# ASCII_13_USB3_0_power.net
KiCad netlist of a schematic drawn in Altium Designer
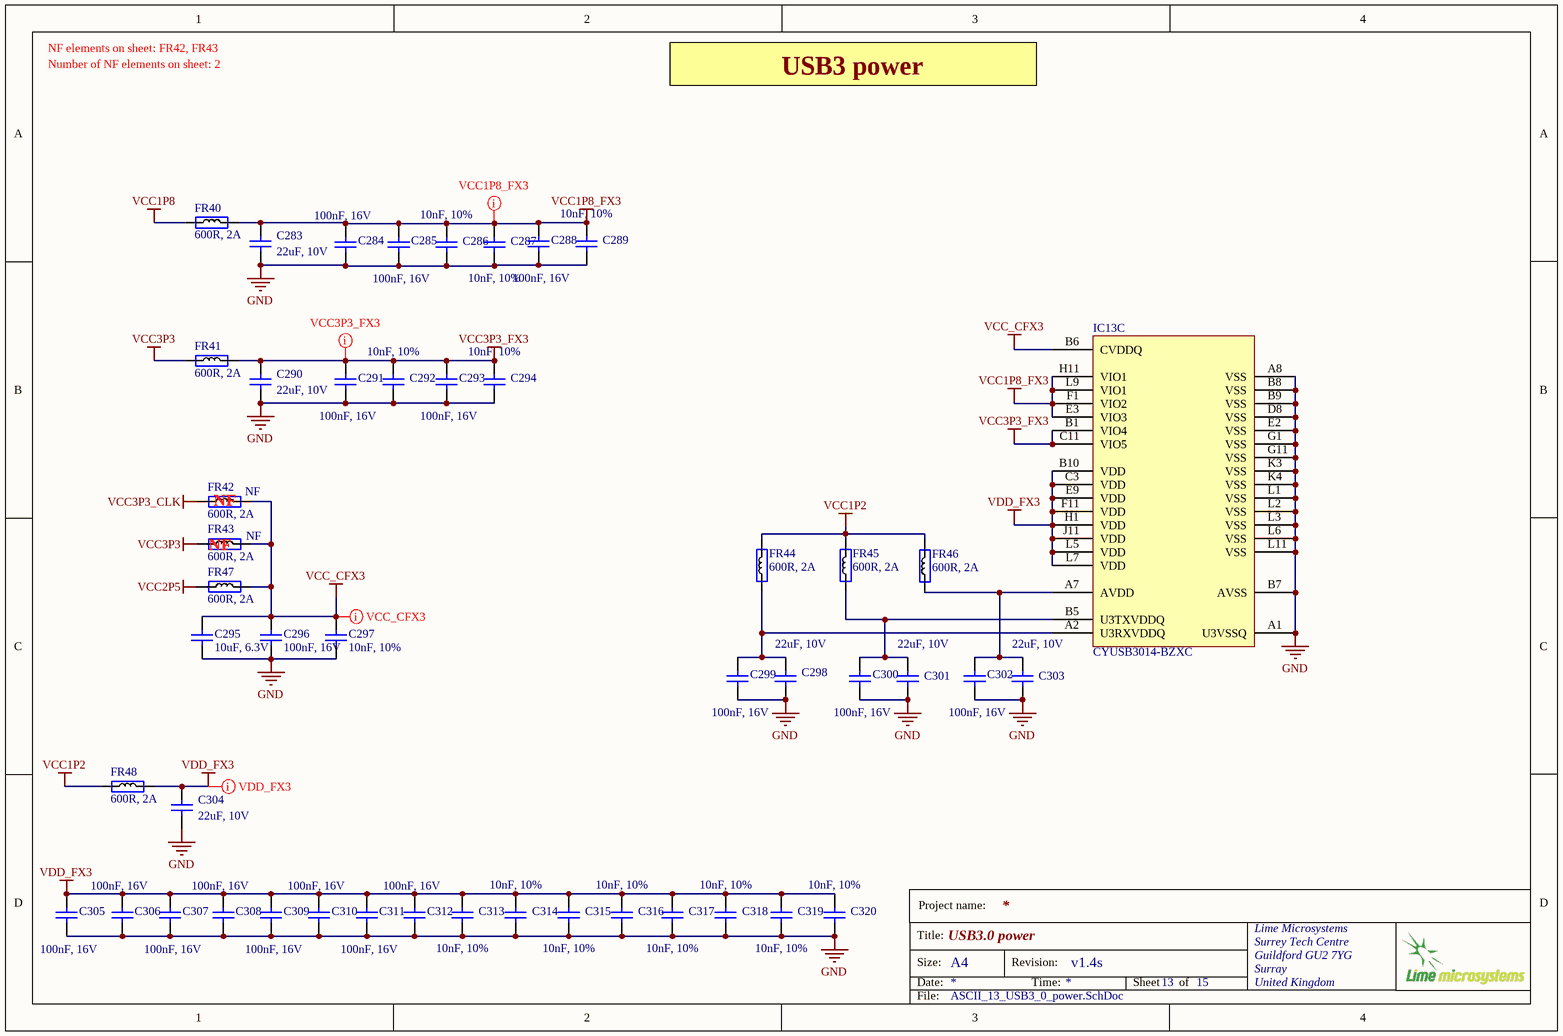
[diagram p0: ASCII_13_USB3_0_power.SchDoc]

(export (version "E")
  (design (tool "Eeschema 10.0.6"))
  (components
    (comp (ref "C283")
      (value "22uF, 10V")
      (footprint "CAP0603")
      (fields (field (name "TOLERANCE") "20 %") (field (name "MANUFACTURER") "TDK"))
      (libsource (lib "LimeFPGAboard_schLib") (part "Cap_0603"))
    )
    (comp (ref "C284")
      (value "100nF, 16V")
      (footprint "CAP0402")
      (fields
        (field (name "TOLERANCE") "10 %")
        (field (name "MANUFACTURER") "Murata Electronics")
        (field (name "MANUFACTURER PART NUMBER") "GRM155R71C104KA88D")
      )
      (libsource (lib "LimeFPGAboard_schLib") (part "Cap_0603"))
    )
    (comp (ref "C285")
      (value "100nF, 16V")
      (footprint "CAP0402")
      (fields
        (field (name "TOLERANCE") "10 %")
        (field (name "MANUFACTURER") "Murata Electronics")
        (field (name "MANUFACTURER PART NUMBER") "GRM155R71C104KA88D")
      )
      (libsource (lib "LimeFPGAboard_schLib") (part "Cap_0603"))
    )
    (comp (ref "C286")
      (value "10nF, 10%")
      (footprint "CAP0402")
      (fields (field (name "TOLERANCE") "±10%") (field (name "MANUFACTURER") "Yageo"))
      (libsource (lib "LimeFPGAboard_schLib") (part "Cap_0603"))
    )
    (comp (ref "C287")
      (value "10nF, 10%")
      (footprint "CAP0402")
      (fields (field (name "TOLERANCE") "±10%") (field (name "MANUFACTURER") "Yageo"))
      (libsource (lib "LimeFPGAboard_schLib") (part "Cap_0603"))
    )
    (comp (ref "C288")
      (value "100nF, 16V")
      (footprint "CAP0402")
      (fields
        (field (name "TOLERANCE") "10 %")
        (field (name "MANUFACTURER") "Murata Electronics")
        (field (name "MANUFACTURER PART NUMBER") "GRM155R71C104KA88D")
      )
      (libsource (lib "LimeFPGAboard_schLib") (part "Cap_0603"))
    )
    (comp (ref "C289")
      (value "10nF, 10%")
      (footprint "CAP0402")
      (fields (field (name "TOLERANCE") "±10%") (field (name "MANUFACTURER") "Yageo"))
      (libsource (lib "LimeFPGAboard_schLib") (part "Cap_0603"))
    )
    (comp (ref "C290")
      (value "22uF, 10V")
      (footprint "CAP0603")
      (fields (field (name "TOLERANCE") "20 %") (field (name "MANUFACTURER") "TDK"))
      (libsource (lib "LimeFPGAboard_schLib") (part "Cap_0603"))
    )
    (comp (ref "C291")
      (value "100nF, 16V")
      (footprint "CAP0402")
      (fields
        (field (name "TOLERANCE") "10 %")
        (field (name "MANUFACTURER") "Murata Electronics")
        (field (name "MANUFACTURER PART NUMBER") "GRM155R71C104KA88D")
      )
      (libsource (lib "LimeFPGAboard_schLib") (part "Cap_0603"))
    )
    (comp (ref "C292")
      (value "10nF, 10%")
      (footprint "CAP0402")
      (fields (field (name "TOLERANCE") "±10%") (field (name "MANUFACTURER") "Yageo"))
      (libsource (lib "LimeFPGAboard_schLib") (part "Cap_0603"))
    )
    (comp (ref "C293")
      (value "100nF, 16V")
      (footprint "CAP0402")
      (fields
        (field (name "TOLERANCE") "10 %")
        (field (name "MANUFACTURER") "Murata Electronics")
        (field (name "MANUFACTURER PART NUMBER") "GRM155R71C104KA88D")
      )
      (libsource (lib "LimeFPGAboard_schLib") (part "Cap_0603"))
    )
    (comp (ref "C294")
      (value "10nF, 10%")
      (footprint "CAP0402")
      (fields (field (name "TOLERANCE") "±10%") (field (name "MANUFACTURER") "Yageo"))
      (libsource (lib "LimeFPGAboard_schLib") (part "Cap_0603"))
    )
    (comp (ref "C295")
      (value "10uF, 6.3V")
      (footprint "CAP0603")
      (fields (field (name "TOLERANCE") "±20%") (field (name "MANUFACTURER") "Yageo"))
      (libsource (lib "LimeFPGAboard_schLib") (part "Cap_0603"))
    )
    (comp (ref "C296")
      (value "100nF, 16V")
      (footprint "CAP0402")
      (fields
        (field (name "TOLERANCE") "10 %")
        (field (name "MANUFACTURER") "Murata Electronics")
        (field (name "MANUFACTURER PART NUMBER") "GRM155R71C104KA88D")
      )
      (libsource (lib "LimeFPGAboard_schLib") (part "Cap_0603"))
    )
    (comp (ref "C297")
      (value "10nF, 10%")
      (footprint "CAP0402")
      (fields (field (name "TOLERANCE") "±10%") (field (name "MANUFACTURER") "Yageo"))
      (libsource (lib "LimeFPGAboard_schLib") (part "Cap_0603"))
    )
    (comp (ref "C298")
      (value "22uF, 10V")
      (footprint "CAP0603")
      (fields (field (name "TOLERANCE") "20 %") (field (name "MANUFACTURER") "TDK"))
      (libsource (lib "LimeFPGAboard_schLib") (part "Cap_0603"))
    )
    (comp (ref "C299")
      (value "100nF, 16V")
      (footprint "CAP0402")
      (fields
        (field (name "TOLERANCE") "10 %")
        (field (name "MANUFACTURER") "Murata Electronics")
        (field (name "MANUFACTURER PART NUMBER") "GRM155R71C104KA88D")
      )
      (libsource (lib "LimeFPGAboard_schLib") (part "Cap_0603"))
    )
    (comp (ref "C300")
      (value "100nF, 16V")
      (footprint "CAP0402")
      (fields
        (field (name "TOLERANCE") "10 %")
        (field (name "MANUFACTURER") "Murata Electronics")
        (field (name "MANUFACTURER PART NUMBER") "GRM155R71C104KA88D")
      )
      (libsource (lib "LimeFPGAboard_schLib") (part "Cap_0603"))
    )
    (comp (ref "C301")
      (value "22uF, 10V")
      (footprint "CAP0603")
      (fields (field (name "TOLERANCE") "20 %") (field (name "MANUFACTURER") "TDK"))
      (libsource (lib "LimeFPGAboard_schLib") (part "Cap_0603"))
    )
    (comp (ref "C302")
      (value "100nF, 16V")
      (footprint "CAP0402")
      (fields
        (field (name "TOLERANCE") "10 %")
        (field (name "MANUFACTURER") "Murata Electronics")
        (field (name "MANUFACTURER PART NUMBER") "GRM155R71C104KA88D")
      )
      (libsource (lib "LimeFPGAboard_schLib") (part "Cap_0603"))
    )
    (comp (ref "C303")
      (value "22uF, 10V")
      (footprint "CAP0603")
      (fields (field (name "TOLERANCE") "20 %") (field (name "MANUFACTURER") "TDK"))
      (libsource (lib "LimeFPGAboard_schLib") (part "Cap_0603"))
    )
    (comp (ref "C304")
      (value "22uF, 10V")
      (footprint "CAP0603")
      (fields (field (name "TOLERANCE") "20 %") (field (name "MANUFACTURER") "TDK"))
      (libsource (lib "LimeFPGAboard_schLib") (part "Cap_0603"))
    )
    (comp (ref "C305")
      (value "100nF, 16V")
      (footprint "CAP0402")
      (fields
        (field (name "TOLERANCE") "10 %")
        (field (name "MANUFACTURER") "Murata Electronics")
        (field (name "MANUFACTURER PART NUMBER") "GRM155R71C104KA88D")
      )
      (libsource (lib "LimeFPGAboard_schLib") (part "Cap_0603"))
    )
    (comp (ref "C306")
      (value "100nF, 16V")
      (footprint "CAP0402")
      (fields
        (field (name "TOLERANCE") "10 %")
        (field (name "MANUFACTURER") "Murata Electronics")
        (field (name "MANUFACTURER PART NUMBER") "GRM155R71C104KA88D")
      )
      (libsource (lib "LimeFPGAboard_schLib") (part "Cap_0603"))
    )
    (comp (ref "C307")
      (value "100nF, 16V")
      (footprint "CAP0402")
      (fields
        (field (name "TOLERANCE") "10 %")
        (field (name "MANUFACTURER") "Murata Electronics")
        (field (name "MANUFACTURER PART NUMBER") "GRM155R71C104KA88D")
      )
      (libsource (lib "LimeFPGAboard_schLib") (part "Cap_0603"))
    )
    (comp (ref "C308")
      (value "100nF, 16V")
      (footprint "CAP0402")
      (fields
        (field (name "TOLERANCE") "10 %")
        (field (name "MANUFACTURER") "Murata Electronics")
        (field (name "MANUFACTURER PART NUMBER") "GRM155R71C104KA88D")
      )
      (libsource (lib "LimeFPGAboard_schLib") (part "Cap_0603"))
    )
    (comp (ref "C309")
      (value "100nF, 16V")
      (footprint "CAP0402")
      (fields
        (field (name "TOLERANCE") "10 %")
        (field (name "MANUFACTURER") "Murata Electronics")
        (field (name "MANUFACTURER PART NUMBER") "GRM155R71C104KA88D")
      )
      (libsource (lib "LimeFPGAboard_schLib") (part "Cap_0603"))
    )
    (comp (ref "C310")
      (value "100nF, 16V")
      (footprint "CAP0402")
      (fields
        (field (name "TOLERANCE") "10 %")
        (field (name "MANUFACTURER") "Murata Electronics")
        (field (name "MANUFACTURER PART NUMBER") "GRM155R71C104KA88D")
      )
      (libsource (lib "LimeFPGAboard_schLib") (part "Cap_0603"))
    )
    (comp (ref "C311")
      (value "100nF, 16V")
      (footprint "CAP0402")
      (fields
        (field (name "TOLERANCE") "10 %")
        (field (name "MANUFACTURER") "Murata Electronics")
        (field (name "MANUFACTURER PART NUMBER") "GRM155R71C104KA88D")
      )
      (libsource (lib "LimeFPGAboard_schLib") (part "Cap_0603"))
    )
    (comp (ref "C312")
      (value "100nF, 16V")
      (footprint "CAP0402")
      (fields
        (field (name "TOLERANCE") "10 %")
        (field (name "MANUFACTURER") "Murata Electronics")
        (field (name "MANUFACTURER PART NUMBER") "GRM155R71C104KA88D")
      )
      (libsource (lib "LimeFPGAboard_schLib") (part "Cap_0603"))
    )
    (comp (ref "C313")
      (value "10nF, 10%")
      (footprint "CAP0402")
      (fields (field (name "TOLERANCE") "±10%") (field (name "MANUFACTURER") "Yageo"))
      (libsource (lib "LimeFPGAboard_schLib") (part "Cap_0603"))
    )
    (comp (ref "C314")
      (value "10nF, 10%")
      (footprint "CAP0402")
      (fields (field (name "TOLERANCE") "±10%") (field (name "MANUFACTURER") "Yageo"))
      (libsource (lib "LimeFPGAboard_schLib") (part "Cap_0603"))
    )
    (comp (ref "C315")
      (value "10nF, 10%")
      (footprint "CAP0402")
      (fields (field (name "TOLERANCE") "±10%") (field (name "MANUFACTURER") "Yageo"))
      (libsource (lib "LimeFPGAboard_schLib") (part "Cap_0603"))
    )
    (comp (ref "C316")
      (value "10nF, 10%")
      (footprint "CAP0402")
      (fields (field (name "TOLERANCE") "±10%") (field (name "MANUFACTURER") "Yageo"))
      (libsource (lib "LimeFPGAboard_schLib") (part "Cap_0603"))
    )
    (comp (ref "C317")
      (value "10nF, 10%")
      (footprint "CAP0402")
      (fields (field (name "TOLERANCE") "±10%") (field (name "MANUFACTURER") "Yageo"))
      (libsource (lib "LimeFPGAboard_schLib") (part "Cap_0603"))
    )
    (comp (ref "C318")
      (value "10nF, 10%")
      (footprint "CAP0402")
      (fields (field (name "TOLERANCE") "±10%") (field (name "MANUFACTURER") "Yageo"))
      (libsource (lib "LimeFPGAboard_schLib") (part "Cap_0603"))
    )
    (comp (ref "C319")
      (value "10nF, 10%")
      (footprint "CAP0402")
      (fields (field (name "TOLERANCE") "±10%") (field (name "MANUFACTURER") "Yageo"))
      (libsource (lib "LimeFPGAboard_schLib") (part "Cap_0603"))
    )
    (comp (ref "C320")
      (value "10nF, 10%")
      (footprint "CAP0402")
      (fields (field (name "TOLERANCE") "±10%") (field (name "MANUFACTURER") "Yageo"))
      (libsource (lib "LimeFPGAboard_schLib") (part "Cap_0603"))
    )
    (comp (ref "FR40")
      (value "600R, 2A")
      (footprint "RES0805")
      (fields (field (name "MANUFACTURER") "TDK Corporation"))
      (libsource (lib "") (part "Ferrite_1"))
    )
    (comp (ref "FR41")
      (value "600R, 2A")
      (footprint "RES0805")
      (fields (field (name "MANUFACTURER") "TDK Corporation"))
      (libsource (lib "") (part "Ferrite_1"))
    )
    (comp (ref "FR42")
      (value "600R, 2A")
      (footprint "RES0805")
      (fields (field (name "MANUFACTURER") "TDK Corporation") (field (name "ASSEMBLY INFO") "NF"))
      (libsource (lib "LimeFPGAboard_schLib") (part "Ferrite"))
    )
    (comp (ref "FR43")
      (value "600R, 2A")
      (footprint "RES0805")
      (fields (field (name "MANUFACTURER") "TDK Corporation") (field (name "ASSEMBLY INFO") "NF"))
      (libsource (lib "LimeFPGAboard_schLib") (part "Ferrite"))
    )
    (comp (ref "FR44")
      (value "600R, 2A")
      (footprint "RES0805")
      (fields (field (name "MANUFACTURER") "TDK Corporation"))
      (libsource (lib "") (part "Ferrite_1"))
    )
    (comp (ref "FR45")
      (value "600R, 2A")
      (footprint "RES0805")
      (fields (field (name "MANUFACTURER") "TDK Corporation"))
      (libsource (lib "") (part "Ferrite_1"))
    )
    (comp (ref "FR46")
      (value "600R, 2A")
      (footprint "RES0805")
      (fields (field (name "MANUFACTURER") "TDK Corporation"))
      (libsource (lib "") (part "Ferrite_1"))
    )
    (comp (ref "FR47")
      (value "600R, 2A")
      (footprint "RES0805")
      (fields (field (name "MANUFACTURER") "TDK Corporation"))
      (libsource (lib "LimeFPGAboard_schLib") (part "Ferrite"))
    )
    (comp (ref "FR48")
      (value "600R, 2A")
      (footprint "RES0805")
      (fields (field (name "MANUFACTURER") "TDK Corporation"))
      (libsource (lib "") (part "Ferrite_1"))
    )
    (comp (ref "IC13")
      (value "CYUSB3014-BZXC")
      (footprint "CYP-BZX121")
      (description "EZ-USB(R) FX3: SuperSpeed USB Controller, 512 KB, 60 I/Os, 0 to 70 degC, 121-Pin FBGA (BZX121)")
      (fields (field (name "MANUFACTURER") "Cypress Semiconductor Corp"))
      (libsource (lib "LimeMicroAltiumLib_schLib") (part "CYUSB3014-BZXC"))
    )
  )
  (nets
    (net (code "1") (name "GND") (class "Default")
      (node (ref "C283") (pin "1") (pinfunction "1_1") (pintype "passive"))
      (node (ref "C284") (pin "2") (pinfunction "2_2") (pintype "passive"))
      (node (ref "C285") (pin "2") (pinfunction "2_2") (pintype "passive"))
      (node (ref "C286") (pin "1") (pinfunction "1_1") (pintype "passive"))
      (node (ref "C287") (pin "1") (pinfunction "1_1") (pintype "passive"))
      (node (ref "C288") (pin "2") (pinfunction "2_2") (pintype "passive"))
      (node (ref "C289") (pin "1") (pinfunction "1_1") (pintype "passive"))
      (node (ref "C290") (pin "1") (pinfunction "1_1") (pintype "passive"))
      (node (ref "C291") (pin "2") (pinfunction "2_2") (pintype "passive"))
      (node (ref "C292") (pin "1") (pinfunction "1_1") (pintype "passive"))
      (node (ref "C293") (pin "2") (pinfunction "2_2") (pintype "passive"))
      (node (ref "C294") (pin "1") (pinfunction "1_1") (pintype "passive"))
      (node (ref "C295") (pin "1") (pinfunction "1_1") (pintype "passive"))
      (node (ref "C296") (pin "2") (pinfunction "2_2") (pintype "passive"))
      (node (ref "C297") (pin "1") (pinfunction "1_1") (pintype "passive"))
      (node (ref "C298") (pin "1") (pinfunction "1_1") (pintype "passive"))
      (node (ref "C299") (pin "2") (pinfunction "2_2") (pintype "passive"))
      (node (ref "C300") (pin "2") (pinfunction "2_2") (pintype "passive"))
      (node (ref "C301") (pin "1") (pinfunction "1_1") (pintype "passive"))
      (node (ref "C302") (pin "2") (pinfunction "2_2") (pintype "passive"))
      (node (ref "C303") (pin "1") (pinfunction "1_1") (pintype "passive"))
      (node (ref "C304") (pin "1") (pinfunction "1_1") (pintype "passive"))
      (node (ref "C305") (pin "2") (pinfunction "2_2") (pintype "passive"))
      (node (ref "C306") (pin "2") (pinfunction "2_2") (pintype "passive"))
      (node (ref "C307") (pin "2") (pinfunction "2_2") (pintype "passive"))
      (node (ref "C308") (pin "2") (pinfunction "2_2") (pintype "passive"))
      (node (ref "C309") (pin "2") (pinfunction "2_2") (pintype "passive"))
      (node (ref "C310") (pin "2") (pinfunction "2_2") (pintype "passive"))
      (node (ref "C311") (pin "2") (pinfunction "2_2") (pintype "passive"))
      (node (ref "C312") (pin "2") (pinfunction "2_2") (pintype "passive"))
      (node (ref "C313") (pin "1") (pinfunction "1_1") (pintype "passive"))
      (node (ref "C314") (pin "1") (pinfunction "1_1") (pintype "passive"))
      (node (ref "C315") (pin "1") (pinfunction "1_1") (pintype "passive"))
      (node (ref "C316") (pin "1") (pinfunction "1_1") (pintype "passive"))
      (node (ref "C317") (pin "1") (pinfunction "1_1") (pintype "passive"))
      (node (ref "C318") (pin "1") (pinfunction "1_1") (pintype "passive"))
      (node (ref "C319") (pin "1") (pinfunction "1_1") (pintype "passive"))
      (node (ref "C320") (pin "1") (pinfunction "1_1") (pintype "passive"))
      (node (ref "IC13") (pin "A1") (pinfunction "U3VSSQ_A1") (pintype "power_in"))
      (node (ref "IC13") (pin "A8") (pinfunction "VSS_A8") (pintype "power_in"))
      (node (ref "IC13") (pin "B7") (pinfunction "AVSS_B7") (pintype "power_in"))
      (node (ref "IC13") (pin "B8") (pinfunction "VSS_B8") (pintype "power_in"))
      (node (ref "IC13") (pin "B9") (pinfunction "VSS_B9") (pintype "power_in"))
      (node (ref "IC13") (pin "D8") (pinfunction "VSS_D8") (pintype "power_in"))
      (node (ref "IC13") (pin "E2") (pinfunction "VSS_E2") (pintype "power_in"))
      (node (ref "IC13") (pin "G1") (pinfunction "VSS_G1") (pintype "power_in"))
      (node (ref "IC13") (pin "G11") (pinfunction "VSS_G11") (pintype "power_in"))
      (node (ref "IC13") (pin "K3") (pinfunction "VSS_K3") (pintype "power_in"))
      (node (ref "IC13") (pin "K4") (pinfunction "VSS_K4") (pintype "power_in"))
      (node (ref "IC13") (pin "L1") (pinfunction "VSS_L1") (pintype "power_in"))
      (node (ref "IC13") (pin "L11") (pinfunction "VSS_L11") (pintype "power_in"))
      (node (ref "IC13") (pin "L2") (pinfunction "VSS_L2") (pintype "power_in"))
      (node (ref "IC13") (pin "L3") (pinfunction "VSS_L3") (pintype "power_in"))
      (node (ref "IC13") (pin "L6") (pinfunction "VSS_L6") (pintype "power_in"))
    )
    (net (code "2") (name "Net-(IC13C-AVDD)") (class "Default")
      (node (ref "C302") (pin "1") (pinfunction "1_1") (pintype "passive"))
      (node (ref "C303") (pin "2") (pinfunction "2_2") (pintype "passive"))
      (node (ref "FR46") (pin "1") (pinfunction "1_1") (pintype "passive"))
      (node (ref "IC13") (pin "A7") (pinfunction "AVDD_A7") (pintype "power_in"))
    )
    (net (code "3") (name "Net-(IC13C-U3RXVDDQ)") (class "Default")
      (node (ref "C298") (pin "2") (pinfunction "2_2") (pintype "passive"))
      (node (ref "C299") (pin "1") (pinfunction "1_1") (pintype "passive"))
      (node (ref "FR44") (pin "1") (pinfunction "1_1") (pintype "passive"))
      (node (ref "IC13") (pin "A2") (pinfunction "U3RXVDDQ_A2") (pintype "power_in"))
    )
    (net (code "4") (name "Net-(IC13C-U3TXVDDQ)") (class "Default")
      (node (ref "C300") (pin "1") (pinfunction "1_1") (pintype "passive"))
      (node (ref "C301") (pin "2") (pinfunction "2_2") (pintype "passive"))
      (node (ref "FR45") (pin "1") (pinfunction "1_1") (pintype "passive"))
      (node (ref "IC13") (pin "B5") (pinfunction "U3TXVDDQ_B5") (pintype "power_in"))
    )
    (net (code "5") (name "VCC1P2") (class "Default")
      (node (ref "FR44") (pin "2") (pinfunction "2_2") (pintype "passive"))
      (node (ref "FR45") (pin "2") (pinfunction "2_2") (pintype "passive"))
      (node (ref "FR46") (pin "2") (pinfunction "2_2") (pintype "passive"))
      (node (ref "FR48") (pin "1") (pinfunction "1_1") (pintype "passive"))
    )
    (net (code "6") (name "VCC1P8") (class "Default")
      (node (ref "FR40") (pin "1") (pinfunction "1_1") (pintype "passive"))
    )
    (net (code "7") (name "VCC1P8_FX3") (class "Default")
      (node (ref "C283") (pin "2") (pinfunction "2_2") (pintype "passive"))
      (node (ref "C284") (pin "1") (pinfunction "1_1") (pintype "passive"))
      (node (ref "C285") (pin "1") (pinfunction "1_1") (pintype "passive"))
      (node (ref "C286") (pin "2") (pinfunction "2_2") (pintype "passive"))
      (node (ref "C287") (pin "2") (pinfunction "2_2") (pintype "passive"))
      (node (ref "C288") (pin "1") (pinfunction "1_1") (pintype "passive"))
      (node (ref "C289") (pin "2") (pinfunction "2_2") (pintype "passive"))
      (node (ref "FR40") (pin "2") (pinfunction "2_2") (pintype "passive"))
      (node (ref "IC13") (pin "E3") (pinfunction "VIO3_E3") (pintype "power_in"))
      (node (ref "IC13") (pin "F1") (pinfunction "VIO2_F1") (pintype "power_in"))
      (node (ref "IC13") (pin "H11") (pinfunction "VIO1_H11") (pintype "power_in"))
      (node (ref "IC13") (pin "L9") (pinfunction "VIO1_L9") (pintype "power_in"))
    )
    (net (code "8") (name "VCC2P5") (class "Default")
      (node (ref "FR47") (pin "2") (pinfunction "2_2") (pintype "passive"))
    )
    (net (code "9") (name "VCC3P3") (class "Default")
      (node (ref "FR41") (pin "1") (pinfunction "1_1") (pintype "passive"))
      (node (ref "FR43") (pin "2") (pinfunction "2_2") (pintype "passive"))
    )
    (net (code "10") (name "VCC3P3_CLK") (class "Default")
      (node (ref "FR42") (pin "2") (pinfunction "2_2") (pintype "passive"))
    )
    (net (code "11") (name "VCC3P3_FX3") (class "Default")
      (node (ref "C290") (pin "2") (pinfunction "2_2") (pintype "passive"))
      (node (ref "C291") (pin "1") (pinfunction "1_1") (pintype "passive"))
      (node (ref "C292") (pin "2") (pinfunction "2_2") (pintype "passive"))
      (node (ref "C293") (pin "1") (pinfunction "1_1") (pintype "passive"))
      (node (ref "C294") (pin "2") (pinfunction "2_2") (pintype "passive"))
      (node (ref "FR41") (pin "2") (pinfunction "2_2") (pintype "passive"))
      (node (ref "IC13") (pin "B1") (pinfunction "VIO4_B1") (pintype "power_in"))
      (node (ref "IC13") (pin "C11") (pinfunction "VIO5_C11") (pintype "power_in"))
    )
    (net (code "12") (name "VCC_CFX3") (class "Default")
      (node (ref "C295") (pin "2") (pinfunction "2_2") (pintype "passive"))
      (node (ref "C296") (pin "1") (pinfunction "1_1") (pintype "passive"))
      (node (ref "C297") (pin "2") (pinfunction "2_2") (pintype "passive"))
      (node (ref "FR42") (pin "1") (pinfunction "1_1") (pintype "passive"))
      (node (ref "FR43") (pin "1") (pinfunction "1_1") (pintype "passive"))
      (node (ref "FR47") (pin "1") (pinfunction "1_1") (pintype "passive"))
      (node (ref "IC13") (pin "B6") (pinfunction "CVDDQ_B6") (pintype "power_in"))
    )
    (net (code "13") (name "VDD_FX3") (class "Default")
      (node (ref "C304") (pin "2") (pinfunction "2_2") (pintype "passive"))
      (node (ref "C305") (pin "1") (pinfunction "1_1") (pintype "passive"))
      (node (ref "C306") (pin "1") (pinfunction "1_1") (pintype "passive"))
      (node (ref "C307") (pin "1") (pinfunction "1_1") (pintype "passive"))
      (node (ref "C308") (pin "1") (pinfunction "1_1") (pintype "passive"))
      (node (ref "C309") (pin "1") (pinfunction "1_1") (pintype "passive"))
      (node (ref "C310") (pin "1") (pinfunction "1_1") (pintype "passive"))
      (node (ref "C311") (pin "1") (pinfunction "1_1") (pintype "passive"))
      (node (ref "C312") (pin "1") (pinfunction "1_1") (pintype "passive"))
      (node (ref "C313") (pin "2") (pinfunction "2_2") (pintype "passive"))
      (node (ref "C314") (pin "2") (pinfunction "2_2") (pintype "passive"))
      (node (ref "C315") (pin "2") (pinfunction "2_2") (pintype "passive"))
      (node (ref "C316") (pin "2") (pinfunction "2_2") (pintype "passive"))
      (node (ref "C317") (pin "2") (pinfunction "2_2") (pintype "passive"))
      (node (ref "C318") (pin "2") (pinfunction "2_2") (pintype "passive"))
      (node (ref "C319") (pin "2") (pinfunction "2_2") (pintype "passive"))
      (node (ref "C320") (pin "2") (pinfunction "2_2") (pintype "passive"))
      (node (ref "FR48") (pin "2") (pinfunction "2_2") (pintype "passive"))
      (node (ref "IC13") (pin "B10") (pinfunction "VDD_B10") (pintype "power_in"))
      (node (ref "IC13") (pin "C3") (pinfunction "VDD_C3") (pintype "power_in"))
      (node (ref "IC13") (pin "E9") (pinfunction "VDD_E9") (pintype "power_in"))
      (node (ref "IC13") (pin "F11") (pinfunction "VDD_F11") (pintype "power_in"))
      (node (ref "IC13") (pin "H1") (pinfunction "VDD_H1") (pintype "power_in"))
      (node (ref "IC13") (pin "J11") (pinfunction "VDD_J11") (pintype "power_in"))
      (node (ref "IC13") (pin "L5") (pinfunction "VDD_L5") (pintype "power_in"))
      (node (ref "IC13") (pin "L7") (pinfunction "VDD_L7") (pintype "power_in"))
    )
  )
)
